# RoverPower.net
KiCad netlist of a schematic drawn in EAGLE
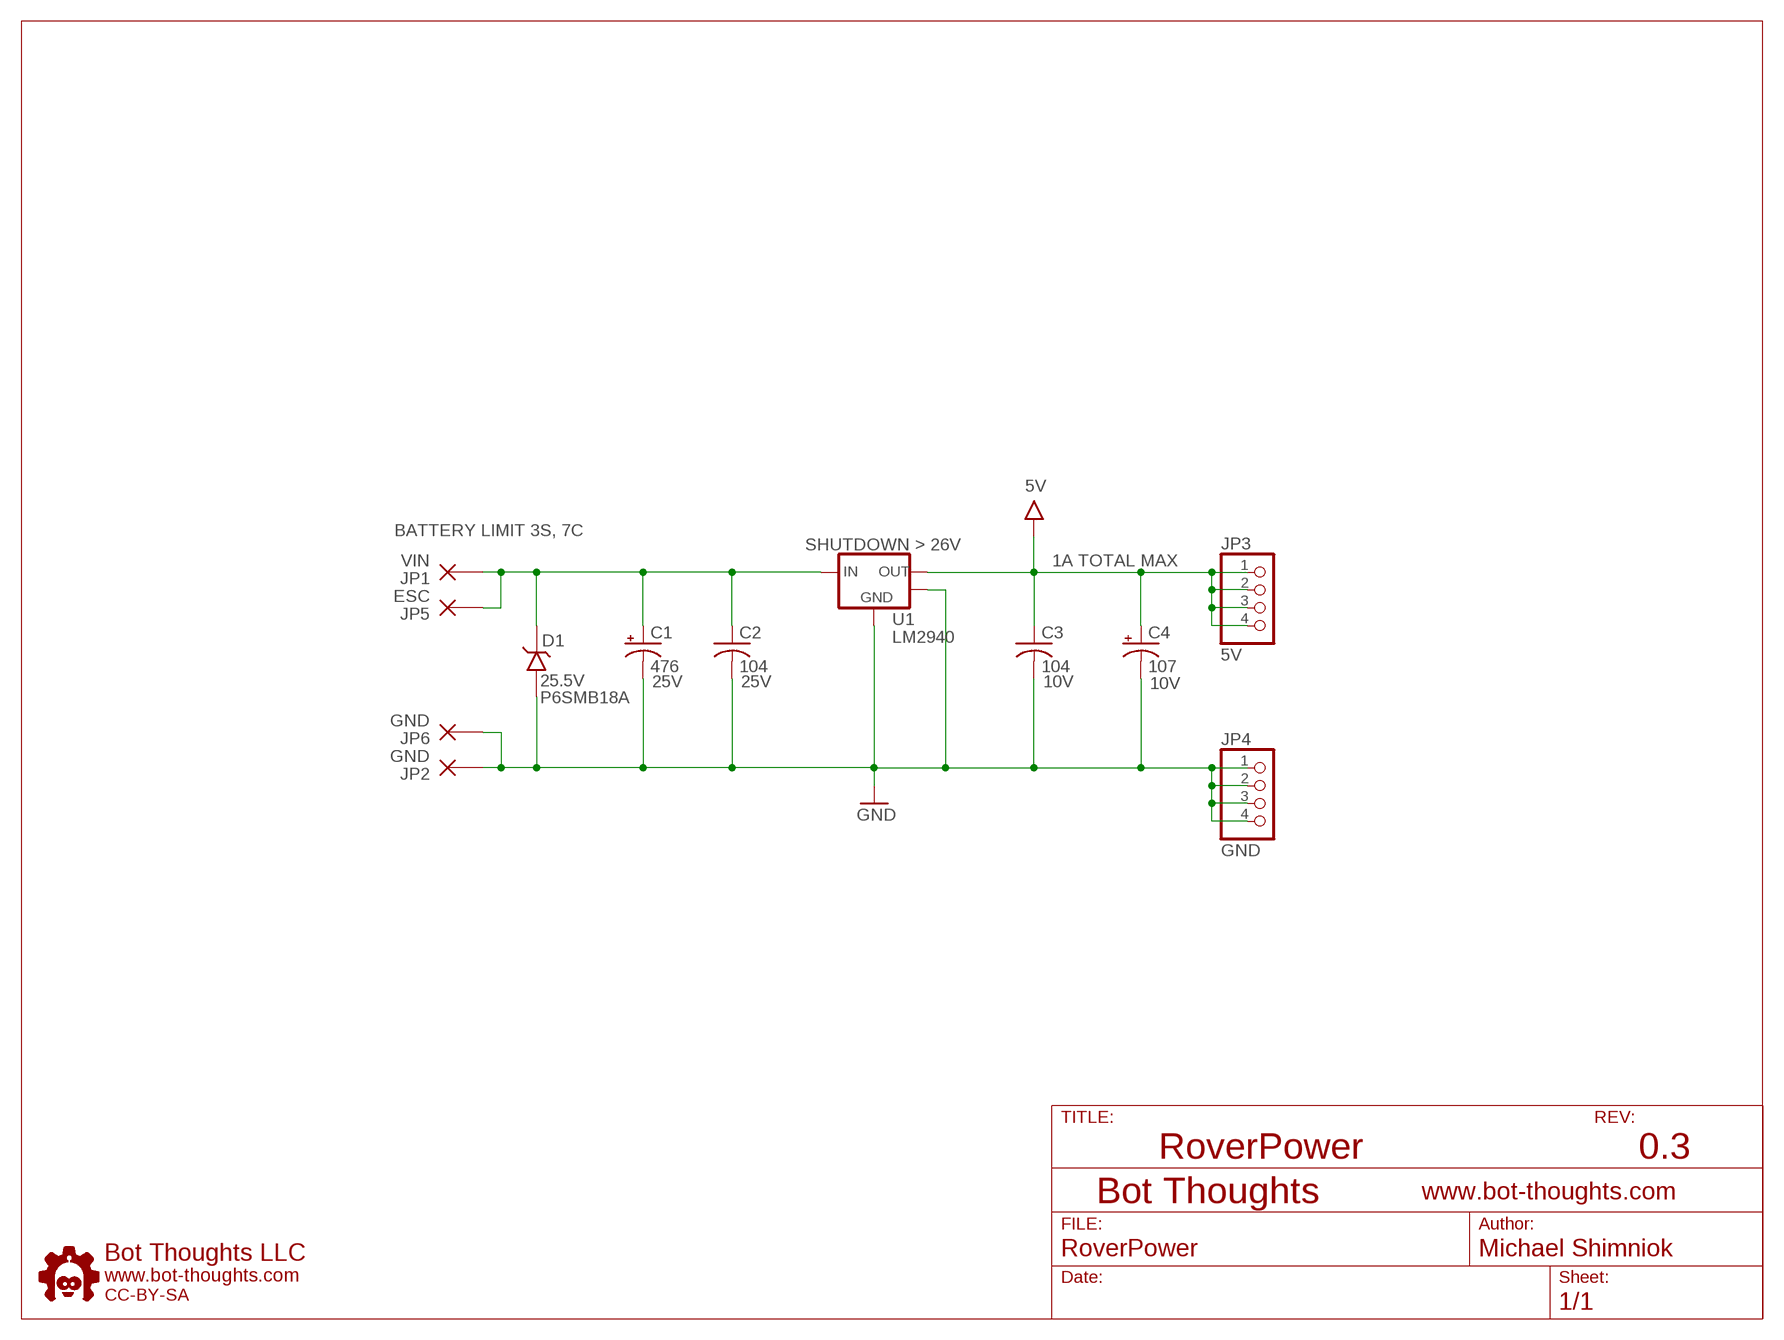
[diagram p0: schematic, sheet 1]

(export (version "E")
  (design (tool "Eeschema 10.0.6"))
  (components
    (comp (ref "C1")
      (value "476")
      (footprint "eagle-import:E2,5-6")
      (fields (field (name "PARTNO") "EEU-FC1H470") (field (name "VOLTAGE") "25V"))
      (libsource (lib "eagle-import") (part "CPOL-USE2.5-6"))
    )
    (comp (ref "C2")
      (value "104")
      (footprint "eagle-import:C0603")
      (fields (field (name "VOLTAGE") "25V"))
      (libsource (lib "eagle-import") (part "C-USC0603"))
    )
    (comp (ref "C3")
      (value "104")
      (footprint "eagle-import:C0603")
      (fields (field (name "VOLTAGE") "10V"))
      (libsource (lib "eagle-import") (part "C-USC0603"))
    )
    (comp (ref "C4")
      (value "107")
      (footprint "eagle-import:SMC_B")
      (fields (field (name "VOLTAGE") "10V"))
      (libsource (lib "eagle-import") (part "CPOL-USSMCB"))
    )
    (comp (ref "D1")
      (value "25.5V")
      (footprint "eagle-import:DO-214AA")
      (fields (field (name "PARTNO") "P6SMB18A"))
      (libsource (lib "eagle-import") (part "P6SMBXXAT3GSMA"))
    )
    (comp (ref "JP1")
      (value "VIN")
      (footprint "eagle-import:PAD_12GA")
      (libsource (lib "eagle-import") (part "WIREPAD_12GA"))
    )
    (comp (ref "JP2")
      (value "GND")
      (footprint "eagle-import:PAD_12GA")
      (libsource (lib "eagle-import") (part "WIREPAD_12GA"))
    )
    (comp (ref "JP3")
      (value "5V")
      (footprint "eagle-import:1X04-S")
      (libsource (lib "eagle-import") (part "PINHD-1X04_2.54-S"))
    )
    (comp (ref "JP4")
      (value "GND")
      (footprint "eagle-import:1X04-S")
      (libsource (lib "eagle-import") (part "PINHD-1X04_2.54-S"))
    )
    (comp (ref "JP5")
      (value "ESC")
      (footprint "eagle-import:PAD_12GA")
      (libsource (lib "eagle-import") (part "WIREPAD_12GA"))
    )
    (comp (ref "JP6")
      (value "GND")
      (footprint "eagle-import:PAD_12GA")
      (libsource (lib "eagle-import") (part "WIREPAD_12GA"))
    )
    (comp (ref "U$2")
      (value "BTLOGO-LOGO-MD")
      (footprint "eagle-import:BTLOGOM")
      (libsource (lib "eagle-import") (part "BTLOGO-LOGO-MD"))
    )
    (comp (ref "U1")
      (value "LM2940")
      (footprint "eagle-import:TO263-3")
      (libsource (lib "eagle-import") (part "LM2940KTT"))
    )
  )
  (nets
    (net (code "1") (name "5V") (class "Default")
      (node (ref "C3") (pin "1") (pinfunction "1_1") (pintype "passive"))
      (node (ref "C4") (pin "+") (pinfunction "+_+") (pintype "passive"))
      (node (ref "JP3") (pin "1") (pinfunction "1_1") (pintype "passive"))
      (node (ref "JP3") (pin "2") (pinfunction "2_2") (pintype "passive"))
      (node (ref "JP3") (pin "3") (pinfunction "3_3") (pintype "passive"))
      (node (ref "JP3") (pin "4") (pinfunction "4_4") (pintype "passive"))
      (node (ref "U1") (pin "3") (pinfunction "VOUT_3") (pintype "bidirectional"))
    )
    (net (code "2") (name "GND") (class "Default")
      (node (ref "C1") (pin "-") (pinfunction "-_-") (pintype "passive"))
      (node (ref "C2") (pin "2") (pinfunction "2_2") (pintype "passive"))
      (node (ref "C3") (pin "2") (pinfunction "2_2") (pintype "passive"))
      (node (ref "C4") (pin "-") (pinfunction "-_-") (pintype "passive"))
      (node (ref "D1") (pin "P$2") (pinfunction "A_P$2") (pintype "passive"))
      (node (ref "JP2") (pin "P$1") (pinfunction "P_P$1") (pintype "bidirectional"))
      (node (ref "JP4") (pin "1") (pinfunction "1_1") (pintype "passive"))
      (node (ref "JP4") (pin "2") (pinfunction "2_2") (pintype "passive"))
      (node (ref "JP4") (pin "3") (pinfunction "3_3") (pintype "passive"))
      (node (ref "JP4") (pin "4") (pinfunction "4_4") (pintype "passive"))
      (node (ref "JP6") (pin "P$1") (pinfunction "P_P$1") (pintype "bidirectional"))
      (node (ref "U1") (pin "2") (pinfunction "GND_2") (pintype "bidirectional"))
      (node (ref "U1") (pin "4") (pinfunction "TAB_4") (pintype "bidirectional"))
    )
    (net (code "3") (name "Net-(D1-C)") (class "Default")
      (node (ref "C1") (pin "+") (pinfunction "+_+") (pintype "passive"))
      (node (ref "C2") (pin "1") (pinfunction "1_1") (pintype "passive"))
      (node (ref "D1") (pin "P$1") (pinfunction "C_P$1") (pintype "passive"))
      (node (ref "JP1") (pin "P$1") (pinfunction "P_P$1") (pintype "bidirectional"))
      (node (ref "JP5") (pin "P$1") (pinfunction "P_P$1") (pintype "bidirectional"))
      (node (ref "U1") (pin "1") (pinfunction "VIN_1") (pintype "bidirectional"))
    )
  )
)
